# Vs1838_IR.net
KiCad netlist of a schematic drawn in Altium Designer
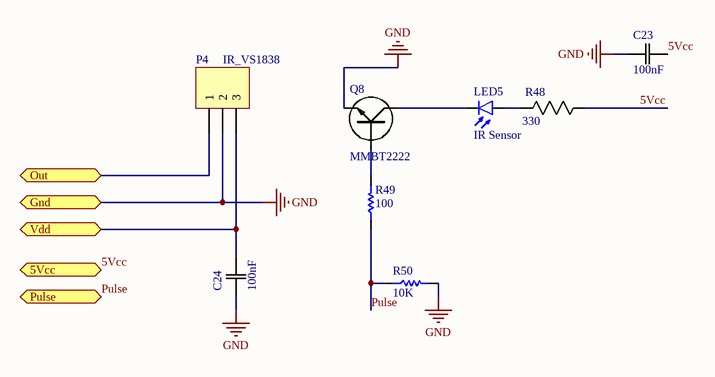
[diagram p0: Vs1838_IR.SchDoc]

(export (version "E")
  (design (tool "Eeschema 10.0.6"))
  (components
    (comp (ref "C23")
      (value "100nF")
      (footprint "0805")
      (description "CAP CER 0.1UF 50V X7R 0805")
      (fields (field (name "TOLERANCE") "10%"))
      (libsource (lib "AltiumLibraries") (part "CAP 470nF 50V"))
    )
    (comp (ref "C24")
      (value "100nF")
      (footprint "0805")
      (description "CAP CER 0.1UF 50V X7R 0805")
      (fields (field (name "TOLERANCE") "10%"))
      (libsource (lib "AltiumLibraries") (part "CAP 470nF 50V"))
    )
    (comp (ref "LED5")
      (value "IR Sensor")
      (footprint "LED5mm_IR")
      (description "Infra Red Reciever Photo Diode")
      (fields (field (name "DESIGNER") "Saeid Jorablo"))
      (libsource (lib "Altium") (part "LED IR"))
    )
    (comp (ref "P4")
      (value "IR_VS1838")
      (footprint "HDR1X3")
      (description "Header, 3-Pin")
      (fields (field (name "PUBLISHER") "Altium Limited"))
      (libsource (lib "Miscellaneous Connectors") (part "Header 3"))
    )
    (comp (ref "Q8")
      (value "MMBT2222")
      (footprint "SOT23-BCE")
      (description "BC847 SMALL SIGNAL NPN TRANSISTOR")
      (libsource (lib "vh_altium_library") (part "MMBT2222"))
    )
    (comp (ref "R48")
      (value "330")
      (footprint "0805")
      (description "RES SMD 330 OHM 1% 1/8W 0805")
      (fields (field (name "TOLERANCE") "1%"))
      (libsource (lib "AltiumLibraries") (part "RES 330.0 1/8W - 1%"))
    )
    (comp (ref "R49")
      (value "100")
      (footprint "RES 0805 (2012X06L)")
      (description "Resistor")
      (fields (field (name "TOLERANCE") "5%") (field (name "POWER") "1/8 W"))
      (libsource (lib "Electrovolt Lib") (part "Resistor"))
    )
    (comp (ref "R50")
      (value "10K")
      (footprint "RES 0805 (2012X06L)")
      (description "Resistor")
      (fields (field (name "TOLERANCE") "5%") (field (name "POWER") "1/8 W"))
      (libsource (lib "Electrovolt Lib") (part "Resistor"))
    )
  )
  (nets
    (net (code "1") (name "/5Vcc") (class "Default")
      (node (ref "C23") (pin "2") (pinfunction "C2_2") (pintype "passive"))
      (node (ref "R48") (pin "1") (pinfunction "R1_1") (pintype "passive"))
    )
    (net (code "2") (name "/Out") (class "Default")
      (node (ref "P4") (pin "1") (pinfunction "1_1") (pintype "passive"))
    )
    (net (code "3") (name "/Pulse") (class "Default")
      (node (ref "R49") (pin "1") (pinfunction "1_1") (pintype "passive"))
      (node (ref "R50") (pin "1") (pinfunction "1_1") (pintype "passive"))
    )
    (net (code "4") (name "/Vdd") (class "Default")
      (node (ref "C24") (pin "2") (pinfunction "C2_2") (pintype "passive"))
      (node (ref "P4") (pin "3") (pinfunction "3_3") (pintype "passive"))
    )
    (net (code "5") (name "GND") (class "Default")
      (node (ref "C23") (pin "1") (pinfunction "C1_1") (pintype "passive"))
      (node (ref "C24") (pin "1") (pinfunction "C1_1") (pintype "passive"))
      (node (ref "P4") (pin "2") (pinfunction "2_2") (pintype "passive"))
      (node (ref "Q8") (pin "E") (pintype "passive"))
      (node (ref "R50") (pin "2") (pinfunction "2_2") (pintype "passive"))
    )
    (net (code "6") (name "Net-(LED5-A)") (class "Default")
      (node (ref "LED5") (pin "1") (pinfunction "A_1") (pintype "passive"))
      (node (ref "R48") (pin "2") (pinfunction "R2_2") (pintype "passive"))
    )
    (net (code "7") (name "Net-(LED5-K)") (class "Default")
      (node (ref "LED5") (pin "2") (pinfunction "K_2") (pintype "passive"))
      (node (ref "Q8") (pin "C") (pintype "passive"))
    )
    (net (code "8") (name "Net-(Q8-PadB)") (class "Default")
      (node (ref "Q8") (pin "B") (pintype "passive"))
      (node (ref "R49") (pin "2") (pinfunction "2_2") (pintype "passive"))
    )
  )
)
